# design.net
KiCad netlist of a schematic drawn in EasyEDA Pro
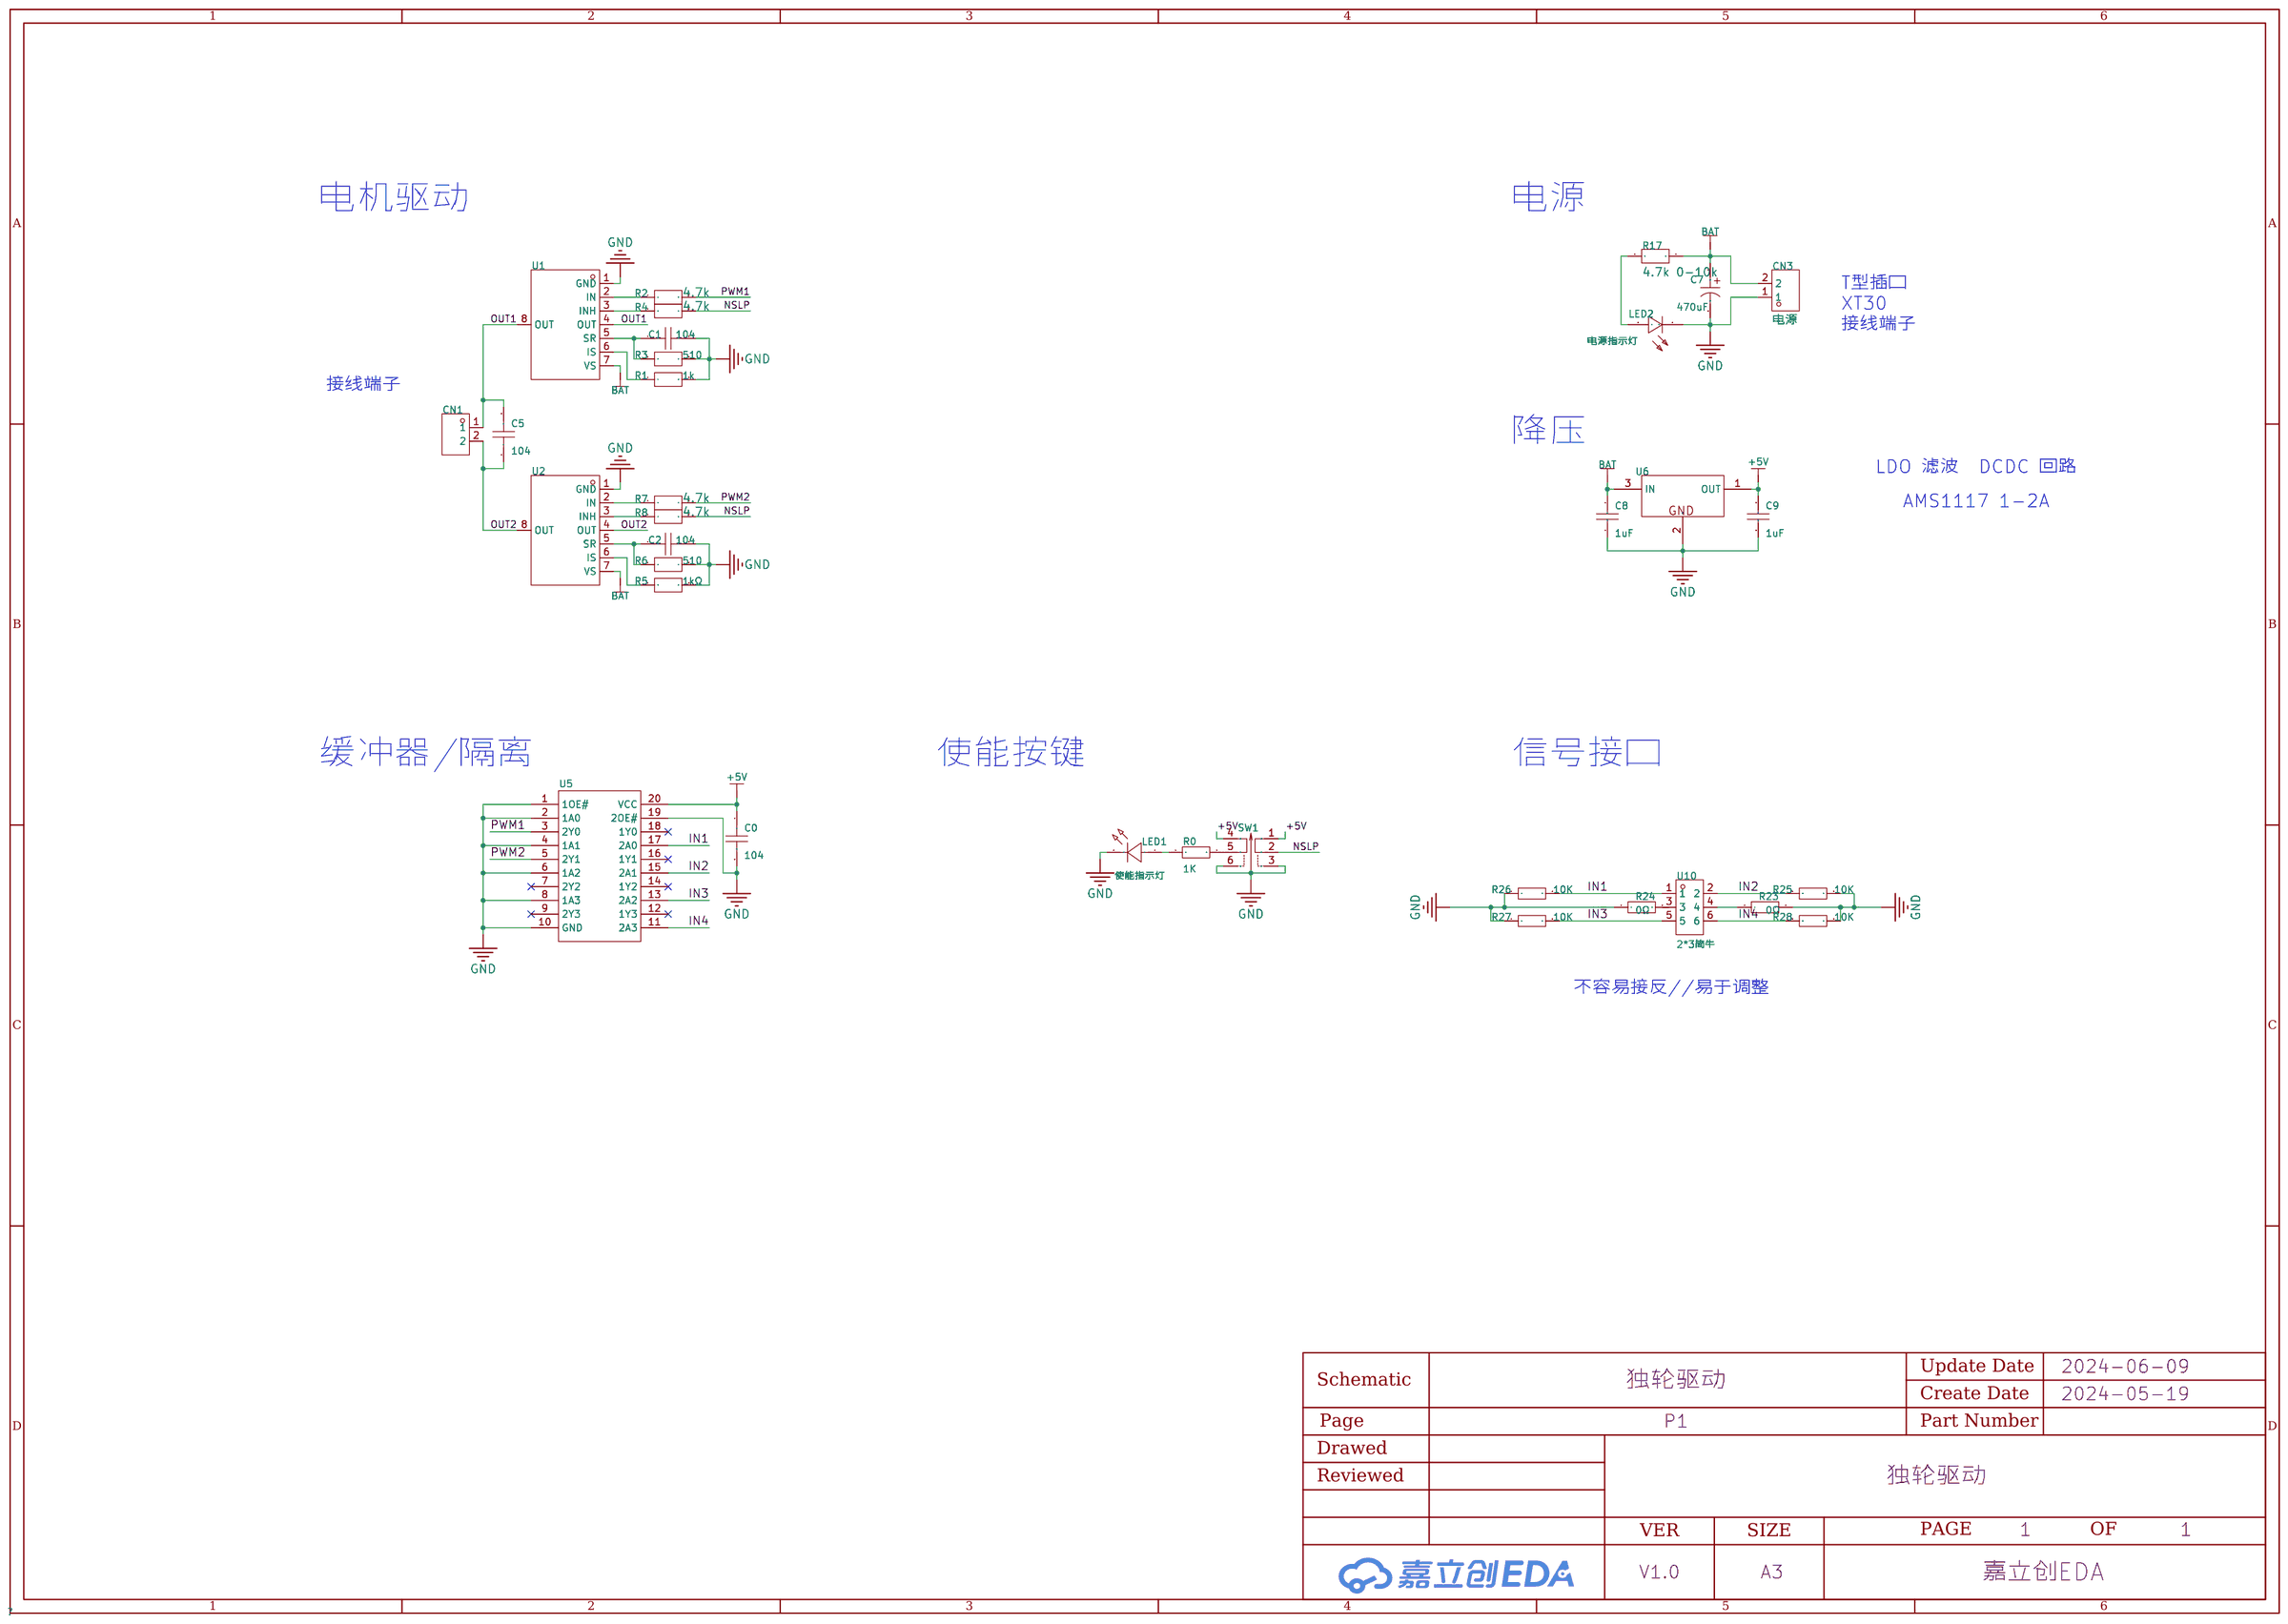
[diagram p0: schematic sheet]

(export (version "E")
  (design (tool "Eeschema 10.0.6"))
  (components
    (comp (ref "C0")
      (value "104")
      (footprint "easyedapro:C0603_1")
      (description "容值:100nF;精度:±10%;额定电压:50V;温度系数:X7R;")
      (libsource (lib "easyedapro") (part "C1210X7R475K630NT"))
    )
    (comp (ref "C1")
      (value "104")
      (footprint "easyedapro:C0603_1")
      (description "容值:100nF;精度:±10%;额定电压:50V;温度系数:X7R;")
      (libsource (lib "easyedapro") (part "C1210X7R475K630NT"))
    )
    (comp (ref "C2")
      (value "104")
      (footprint "easyedapro:C0603_1")
      (description "容值:100nF;精度:±10%;额定电压:50V;温度系数:X7R;")
      (libsource (lib "easyedapro") (part "C1210X7R475K630NT"))
    )
    (comp (ref "C5")
      (value "104")
      (footprint "easyedapro:C0603_1")
      (description "容值:100nF;精度:±10%;额定电压:50V;温度系数:X7R;")
      (libsource (lib "easyedapro") (part "C1210X7R475K630NT"))
    )
    (comp (ref "C7")
      (value "470uF")
      (footprint "easyedapro:CAP-SMD_BD8.0-L8.3-W8.3-LS9.1-FD")
      (description "容值:470uF;精度:±20%;额定电压:25V;电容体直径:-;电容体长度:-;纹波电流:-;等效串联电阻:-;工作寿命:-;")
      (fields (field (name "Manufacturer Part") "RVT1E471M0810") (field (name "Manufacturer") "HONOR(荣誉)"))
      (libsource (lib "easyedapro") (part "RVT1E471M0810"))
    )
    (comp (ref "C8")
      (value "1uF")
      (footprint "easyedapro:C0603_1")
      (description "温度系数:X5R;精度:±10%;额定电压:50V;容值:1uF;")
      (fields
        (field (name "Manufacturer Part") "CL10A105KB8NNNC")
        (field (name "Manufacturer") "SAMSUNG(三星)")
      )
      (libsource (lib "easyedapro") (part "CL10A105KB8NNNC"))
    )
    (comp (ref "C9")
      (value "1uF")
      (footprint "easyedapro:C0603_1")
      (description "温度系数:X5R;精度:±10%;额定电压:50V;容值:1uF;")
      (fields
        (field (name "Manufacturer Part") "CL10A105KB8NNNC")
        (field (name "Manufacturer") "SAMSUNG(三星)")
      )
      (libsource (lib "easyedapro") (part "CL10A105KB8NNNC"))
    )
    (comp (ref "CN1")
      (value "电机1")
      (footprint "easyedapro:CONN-TH_P5.00_KF301-5.0-2P")
      (description "间距:5mm;排数:1;每排PIN数:2;安装方式:直针;额定电流:17A;额定电压:250V;线规 - AWG:14~22;线规 - mm?:1.5;工作温度范围:-30~+120;颜色:蓝色;")
      (fields (field (name "Manufacturer Part") "KF301-5.0-2P") (field (name "Manufacturer") "KEFA(科发)"))
      (libsource (lib "easyedapro") (part "KF301-5.0-2P"))
    )
    (comp (ref "CN3")
      (value "电源")
      (footprint "easyedapro:CONN-TH_P5.00_KF301-5.0-2P")
      (description "间距:5mm;排数:1;每排PIN数:2;安装方式:直针;额定电流:17A;额定电压:250V;线规 - AWG:14~22;线规 - mm?:1.5;工作温度范围:-30~+120;颜色:蓝色;")
      (fields (field (name "Manufacturer Part") "KF301-5.0-2P") (field (name "Manufacturer") "KEFA(科发)"))
      (libsource (lib "easyedapro") (part "KF301-5.0-2P"))
    )
    (comp (ref "LED1")
      (value "使能指示灯")
      (footprint "easyedapro:LED-SMD_L1.6-W0.8-FD_GREEN")
      (fields
        (field (name "Manufacturer Part") "19-213/GVC-AMNB/3T")
        (field (name "Manufacturer") "EVERLIGHT(台湾亿光)")
      )
      (libsource (lib "easyedapro") (part "19-213/GVC-AMNB/3T_C883167"))
    )
    (comp (ref "LED2")
      (value "电源指示灯")
      (footprint "easyedapro:LED0603-RD_RED")
      (description "发光颜色:红灯;")
      (fields (field (name "Manufacturer Part") "NCD0603R1") (field (name "Manufacturer") "国星光电"))
      (libsource (lib "easyedapro") (part "FC-DA1608HRK-620D"))
    )
    (comp (ref "R0") (value "1K") (footprint "easyedapro:R0603") (libsource (lib "easyedapro") (part "电阻")))
    (comp (ref "R1")
      (value "1k")
      (footprint "easyedapro:R0603")
      (description "电阻类型:厚膜电阻;阻值:510Ω;精度:±5%;功率:100mW;温度系数:±100ppm/;最大工作电压:50V;工作温度范围:-55~+155;")
      (fields (field (name "Manufacturer Part") "FRC0603J511 TS") (field (name "Manufacturer") "FOJAN(富捷)"))
      (libsource (lib "easyedapro") (part "FRC0603J511 TS"))
    )
    (comp (ref "R2")
      (value "4.7k")
      (footprint "easyedapro:R0603")
      (fields (field (name "Manufacturer Part") "FRC0603J472 TS") (field (name "Manufacturer") "FOJAN(富捷)"))
      (libsource (lib "easyedapro") (part "FRC0603J472 TS"))
    )
    (comp (ref "R3")
      (value "510")
      (footprint "easyedapro:R0603")
      (description "电阻类型:厚膜电阻;阻值:510Ω;精度:±5%;功率:100mW;温度系数:±100ppm/;最大工作电压:50V;工作温度范围:-55~+155;")
      (fields (field (name "Manufacturer Part") "FRC0603J511 TS") (field (name "Manufacturer") "FOJAN(富捷)"))
      (libsource (lib "easyedapro") (part "FRC0603J511 TS"))
    )
    (comp (ref "R4")
      (value "4.7k")
      (footprint "easyedapro:R0603")
      (fields (field (name "Manufacturer Part") "FRC0603J472 TS") (field (name "Manufacturer") "FOJAN(富捷)"))
      (libsource (lib "easyedapro") (part "FRC0603J472 TS"))
    )
    (comp (ref "R5")
      (value "1kΩ")
      (footprint "easyedapro:R0603")
      (description "电阻类型:厚膜电阻;阻值:1kΩ;精度:±5%;功率:100mW;温度系数:±100ppm/;最大工作电压:50V;工作温度范围:-55~+155;")
      (fields (field (name "Manufacturer Part") "FRC0603J102 TS") (field (name "Manufacturer") "FOJAN(富捷)"))
      (libsource (lib "easyedapro") (part "FRC0603J102 TS"))
    )
    (comp (ref "R6")
      (value "510")
      (footprint "easyedapro:R0603")
      (description "电阻类型:厚膜电阻;阻值:510Ω;精度:±5%;功率:100mW;温度系数:±100ppm/;最大工作电压:50V;工作温度范围:-55~+155;")
      (fields (field (name "Manufacturer Part") "FRC0603J511 TS") (field (name "Manufacturer") "FOJAN(富捷)"))
      (libsource (lib "easyedapro") (part "FRC0603J511 TS"))
    )
    (comp (ref "R7")
      (value "4.7k")
      (footprint "easyedapro:R0603")
      (fields (field (name "Manufacturer Part") "FRC0603J472 TS") (field (name "Manufacturer") "FOJAN(富捷)"))
      (libsource (lib "easyedapro") (part "FRC0603J472 TS"))
    )
    (comp (ref "R8")
      (value "4.7k")
      (footprint "easyedapro:R0603")
      (fields (field (name "Manufacturer Part") "FRC0603J472 TS") (field (name "Manufacturer") "FOJAN(富捷)"))
      (libsource (lib "easyedapro") (part "FRC0603J472 TS"))
    )
    (comp (ref "R17")
      (value "4.7k 0-10k")
      (footprint "easyedapro:R0603")
      (fields (field (name "Manufacturer Part") "FRC0603J472 TS") (field (name "Manufacturer") "FOJAN(富捷)"))
      (libsource (lib "easyedapro") (part "FRC0603J472 TS"))
    )
    (comp (ref "R23")
      (value "0Ω")
      (footprint "easyedapro:R0603")
      (description "电阻类型:厚膜电阻;阻值:0Ω;精度:-;功率:100mW;温度系数:-;最大工作电压:150V;工作温度范围:-55~+155;")
      (fields (field (name "Manufacturer Part") "ERJ3GEY0R00V") (field (name "Manufacturer") "PANASONIC(松下)"))
      (libsource (lib "easyedapro") (part "ERJ-3GEY0R00V"))
    )
    (comp (ref "R24")
      (value "0Ω")
      (footprint "easyedapro:R0603")
      (description "电阻类型:厚膜电阻;阻值:0Ω;精度:-;功率:100mW;温度系数:-;最大工作电压:150V;工作温度范围:-55~+155;")
      (fields (field (name "Manufacturer Part") "ERJ3GEY0R00V") (field (name "Manufacturer") "PANASONIC(松下)"))
      (libsource (lib "easyedapro") (part "ERJ-3GEY0R00V"))
    )
    (comp (ref "R25")
      (value "10K")
      (footprint "easyedapro:R0603")
      (description "电阻类型:厚膜电阻;阻值:0Ω;精度:-;功率:100mW;温度系数:-;最大工作电压:150V;工作温度范围:-55~+155;")
      (fields (field (name "Manufacturer Part") "ERJ3GEY0R00V") (field (name "Manufacturer") "PANASONIC(松下)"))
      (libsource (lib "easyedapro") (part "ERJ-3GEY0R00V"))
    )
    (comp (ref "R26")
      (value "10K")
      (footprint "easyedapro:R0603")
      (description "电阻类型:厚膜电阻;阻值:0Ω;精度:-;功率:100mW;温度系数:-;最大工作电压:150V;工作温度范围:-55~+155;")
      (fields (field (name "Manufacturer Part") "ERJ3GEY0R00V") (field (name "Manufacturer") "PANASONIC(松下)"))
      (libsource (lib "easyedapro") (part "ERJ-3GEY0R00V"))
    )
    (comp (ref "R27")
      (value "10K")
      (footprint "easyedapro:R0603")
      (description "电阻类型:厚膜电阻;阻值:0Ω;精度:-;功率:100mW;温度系数:-;最大工作电压:150V;工作温度范围:-55~+155;")
      (fields (field (name "Manufacturer Part") "ERJ3GEY0R00V") (field (name "Manufacturer") "PANASONIC(松下)"))
      (libsource (lib "easyedapro") (part "ERJ-3GEY0R00V"))
    )
    (comp (ref "R28")
      (value "10K")
      (footprint "easyedapro:R0603")
      (description "电阻类型:厚膜电阻;阻值:0Ω;精度:-;功率:100mW;温度系数:-;最大工作电压:150V;工作温度范围:-55~+155;")
      (fields (field (name "Manufacturer Part") "ERJ3GEY0R00V") (field (name "Manufacturer") "PANASONIC(松下)"))
      (libsource (lib "easyedapro") (part "ERJ-3GEY0R00V"))
    )
    (comp (ref "SW1")
      (value "使能开关")
      (footprint "easyedapro:SW-TH_6P-L5.8-W5.8-P2.00-LS4.5-BL")
      (fields (field (name "Manufacturer Part") "PB22E60L") (field (name "Manufacturer") "CIKI(皓富)"))
      (libsource (lib "easyedapro") (part "PB22E60L"))
    )
    (comp (ref "U1")
      (value "BTN7971BAUMA1")
      (footprint "easyedapro:TO-263-7_L10.2-W10.4-P1.27-LS14.4-BR")
      (fields (field (name "Manufacturer") "Infineon(英飞凌)"))
      (libsource (lib "easyedapro") (part "BTN7971BAUMA1"))
    )
    (comp (ref "U2")
      (value "BTN7971BAUMA1")
      (footprint "easyedapro:TO-263-7_L10.2-W10.4-P1.27-LS14.4-BR")
      (fields (field (name "Manufacturer") "Infineon(英飞凌)"))
      (libsource (lib "easyedapro") (part "BTN7971BAUMA1"))
    )
    (comp (ref "U5")
      (value "74HC244PW,118")
      (footprint "easyedapro:TSSOP-20_L6.5-W4.4-P0.65-LS6.4-BL")
      (fields (field (name "Manufacturer") "Nexperia(安世)"))
      (libsource (lib "easyedapro") (part "74HC244PW,118"))
    )
    (comp (ref "U6")
      (value "~")
      (footprint "easyedapro:SOT-89-3_L4.5-W2.5-P1.50-LS4.2-BR")
      (fields (field (name "Manufacturer Part") "UMW78L05") (field (name "Manufacturer") "UMW(友台半导体)"))
      (libsource (lib "easyedapro") (part "UMW78L05"))
    )
    (comp (ref "U10")
      (value "2*3简牛")
      (footprint "easyedapro:CONN-TH_6P-P2.54_KINGHELM_KH-2.54PH180-2X3P-L8.9")
      (description "连接器类型:简牛座;间距:2.54mm;每排PIN数:3;排数:2;封装形式:直插;")
      (fields (field (name "Manufacturer") "kinghelm(金航标)"))
      (libsource (lib "easyedapro") (part "KH-2.54PH180-2X3P-L8.9"))
    )
  )
  (nets
    (net (code "1") (name "+5V") (class "Default")
      (node (ref "C0") (pin "1") (pinfunction "1_1") (pintype "input"))
      (node (ref "C9") (pin "2") (pinfunction "2_2") (pintype "input"))
      (node (ref "SW1") (pin "1") (pinfunction "1_1") (pintype "input"))
      (node (ref "SW1") (pin "4") (pinfunction "4_4") (pintype "input"))
      (node (ref "U5") (pin "20") (pinfunction "VCC_20") (pintype "input"))
      (node (ref "U6") (pin "1") (pinfunction "OUT_1") (pintype "input"))
    )
    (net (code "2") (name "/IN1") (class "Default")
      (node (ref "R26") (pin "2") (pinfunction "2_2") (pintype "input"))
      (node (ref "U10") (pin "1") (pinfunction "1_1") (pintype "input"))
      (node (ref "U5") (pin "17") (pinfunction "2A0_17") (pintype "input"))
    )
    (net (code "3") (name "/IN2") (class "Default")
      (node (ref "R25") (pin "1") (pinfunction "1_1") (pintype "input"))
      (node (ref "U10") (pin "2") (pinfunction "2_2") (pintype "input"))
      (node (ref "U5") (pin "15") (pinfunction "2A1_15") (pintype "input"))
    )
    (net (code "4") (name "/IN3") (class "Default")
      (node (ref "R27") (pin "2") (pinfunction "2_2") (pintype "input"))
      (node (ref "U10") (pin "5") (pinfunction "5_5") (pintype "input"))
      (node (ref "U5") (pin "13") (pinfunction "2A2_13") (pintype "input"))
    )
    (net (code "5") (name "/IN4") (class "Default")
      (node (ref "R28") (pin "1") (pinfunction "1_1") (pintype "input"))
      (node (ref "U10") (pin "6") (pinfunction "6_6") (pintype "input"))
      (node (ref "U5") (pin "11") (pinfunction "2A3_11") (pintype "input"))
    )
    (net (code "6") (name "/NSLP") (class "Default")
      (node (ref "R4") (pin "2") (pinfunction "2_2") (pintype "input"))
      (node (ref "R8") (pin "2") (pinfunction "2_2") (pintype "input"))
      (node (ref "SW1") (pin "2") (pinfunction "2_2") (pintype "input"))
    )
    (net (code "7") (name "/OUT1") (class "Default")
      (node (ref "C5") (pin "2") (pinfunction "2_2") (pintype "input"))
      (node (ref "CN1") (pin "1") (pinfunction "1_1") (pintype "input"))
      (node (ref "U1") (pin "4") (pinfunction "OUT_4") (pintype "input"))
      (node (ref "U1") (pin "8") (pinfunction "OUT_8") (pintype "input"))
    )
    (net (code "8") (name "/OUT2") (class "Default")
      (node (ref "C5") (pin "1") (pinfunction "1_1") (pintype "input"))
      (node (ref "CN1") (pin "2") (pinfunction "2_2") (pintype "input"))
      (node (ref "U2") (pin "4") (pinfunction "OUT_4") (pintype "input"))
      (node (ref "U2") (pin "8") (pinfunction "OUT_8") (pintype "input"))
    )
    (net (code "9") (name "/PWM1") (class "Default")
      (node (ref "R2") (pin "2") (pinfunction "2_2") (pintype "input"))
      (node (ref "U5") (pin "3") (pinfunction "2Y0_3") (pintype "input"))
    )
    (net (code "10") (name "/PWM2") (class "Default")
      (node (ref "R7") (pin "2") (pinfunction "2_2") (pintype "input"))
      (node (ref "U5") (pin "5") (pinfunction "2Y1_5") (pintype "input"))
    )
    (net (code "11") (name "BAT") (class "Default")
      (node (ref "C7") (pin "1") (pinfunction "1_1") (pintype "input"))
      (node (ref "C8") (pin "2") (pinfunction "2_2") (pintype "input"))
      (node (ref "CN3") (pin "2") (pinfunction "2_2") (pintype "input"))
      (node (ref "R17") (pin "1") (pinfunction "1_1") (pintype "input"))
      (node (ref "U1") (pin "7") (pinfunction "VS_7") (pintype "input"))
      (node (ref "U2") (pin "7") (pinfunction "VS_7") (pintype "input"))
      (node (ref "U6") (pin "3") (pinfunction "IN_3") (pintype "input"))
    )
    (net (code "12") (name "GND") (class "Default")
      (node (ref "C0") (pin "2") (pinfunction "2_2") (pintype "input"))
      (node (ref "C1") (pin "2") (pinfunction "2_2") (pintype "input"))
      (node (ref "C2") (pin "2") (pinfunction "2_2") (pintype "input"))
      (node (ref "C7") (pin "2") (pinfunction "2_2") (pintype "input"))
      (node (ref "C8") (pin "1") (pinfunction "1_1") (pintype "input"))
      (node (ref "C9") (pin "1") (pinfunction "1_1") (pintype "input"))
      (node (ref "CN3") (pin "1") (pinfunction "1_1") (pintype "input"))
      (node (ref "LED1") (pin "2") (pinfunction "A_2") (pintype "input"))
      (node (ref "LED2") (pin "1") (pinfunction "K_1") (pintype "input"))
      (node (ref "R1") (pin "2") (pinfunction "2_2") (pintype "input"))
      (node (ref "R23") (pin "2") (pinfunction "2_2") (pintype "input"))
      (node (ref "R24") (pin "1") (pinfunction "1_1") (pintype "input"))
      (node (ref "R25") (pin "2") (pinfunction "2_2") (pintype "input"))
      (node (ref "R26") (pin "1") (pinfunction "1_1") (pintype "input"))
      (node (ref "R27") (pin "1") (pinfunction "1_1") (pintype "input"))
      (node (ref "R28") (pin "2") (pinfunction "2_2") (pintype "input"))
      (node (ref "R3") (pin "2") (pinfunction "2_2") (pintype "input"))
      (node (ref "R5") (pin "2") (pinfunction "2_2") (pintype "input"))
      (node (ref "R6") (pin "2") (pinfunction "2_2") (pintype "input"))
      (node (ref "SW1") (pin "3") (pinfunction "3_3") (pintype "input"))
      (node (ref "SW1") (pin "6") (pinfunction "6_6") (pintype "input"))
      (node (ref "U1") (pin "1") (pinfunction "GND_1") (pintype "input"))
      (node (ref "U2") (pin "1") (pinfunction "GND_1") (pintype "input"))
      (node (ref "U5") (pin "1") (pinfunction "1OE#_1") (pintype "input"))
      (node (ref "U5") (pin "10") (pinfunction "GND_10") (pintype "input"))
      (node (ref "U5") (pin "19") (pinfunction "2OE#_19") (pintype "input"))
      (node (ref "U5") (pin "2") (pinfunction "1A0_2") (pintype "input"))
      (node (ref "U5") (pin "4") (pinfunction "1A1_4") (pintype "input"))
      (node (ref "U5") (pin "6") (pinfunction "1A2_6") (pintype "input"))
      (node (ref "U5") (pin "8") (pinfunction "1A3_8") (pintype "input"))
      (node (ref "U6") (pin "2") (pinfunction "GND_2") (pintype "input"))
    )
    (net (code "13") (name "Net-(LED1-K)") (class "Default")
      (node (ref "LED1") (pin "1") (pinfunction "K_1") (pintype "input"))
      (node (ref "R0") (pin "1") (pinfunction "1_1") (pintype "input"))
    )
    (net (code "14") (name "Net-(LED2-A)") (class "Default")
      (node (ref "LED2") (pin "2") (pinfunction "A_2") (pintype "input"))
      (node (ref "R17") (pin "2") (pinfunction "2_2") (pintype "input"))
    )
    (net (code "15") (name "Net-(R0-Pad2)") (class "Default")
      (node (ref "R0") (pin "2") (pinfunction "2_2") (pintype "input"))
      (node (ref "SW1") (pin "5") (pinfunction "5_5") (pintype "input"))
    )
    (net (code "16") (name "Net-(R23-Pad1)") (class "Default")
      (node (ref "R23") (pin "1") (pinfunction "1_1") (pintype "input"))
      (node (ref "U10") (pin "4") (pinfunction "4_4") (pintype "input"))
    )
    (net (code "17") (name "Net-(R24-Pad2)") (class "Default")
      (node (ref "R24") (pin "2") (pinfunction "2_2") (pintype "input"))
      (node (ref "U10") (pin "3") (pinfunction "3_3") (pintype "input"))
    )
    (net (code "18") (name "Net-(U1-IN)") (class "Default")
      (node (ref "R2") (pin "1") (pinfunction "1_1") (pintype "input"))
      (node (ref "U1") (pin "2") (pinfunction "IN_2") (pintype "input"))
    )
    (net (code "19") (name "Net-(U1-INH)") (class "Default")
      (node (ref "R4") (pin "1") (pinfunction "1_1") (pintype "input"))
      (node (ref "U1") (pin "3") (pinfunction "INH_3") (pintype "input"))
    )
    (net (code "20") (name "Net-(U1-IS)") (class "Default")
      (node (ref "R1") (pin "1") (pinfunction "1_1") (pintype "input"))
      (node (ref "U1") (pin "6") (pinfunction "IS_6") (pintype "input"))
    )
    (net (code "21") (name "Net-(U1-SR)") (class "Default")
      (node (ref "C1") (pin "1") (pinfunction "1_1") (pintype "input"))
      (node (ref "R3") (pin "1") (pinfunction "1_1") (pintype "input"))
      (node (ref "U1") (pin "5") (pinfunction "SR_5") (pintype "input"))
    )
    (net (code "22") (name "Net-(U2-IN)") (class "Default")
      (node (ref "R7") (pin "1") (pinfunction "1_1") (pintype "input"))
      (node (ref "U2") (pin "2") (pinfunction "IN_2") (pintype "input"))
    )
    (net (code "23") (name "Net-(U2-INH)") (class "Default")
      (node (ref "R8") (pin "1") (pinfunction "1_1") (pintype "input"))
      (node (ref "U2") (pin "3") (pinfunction "INH_3") (pintype "input"))
    )
    (net (code "24") (name "Net-(U2-IS)") (class "Default")
      (node (ref "R5") (pin "1") (pinfunction "1_1") (pintype "input"))
      (node (ref "U2") (pin "6") (pinfunction "IS_6") (pintype "input"))
    )
    (net (code "25") (name "Net-(U2-SR)") (class "Default")
      (node (ref "C2") (pin "1") (pinfunction "1_1") (pintype "input"))
      (node (ref "R6") (pin "1") (pinfunction "1_1") (pintype "input"))
      (node (ref "U2") (pin "5") (pinfunction "SR_5") (pintype "input"))
    )
    (net (code "26") (name "unconnected-(U5-1Y0-Pad18)") (class "Default")
      (node (ref "U5") (pin "18") (pinfunction "1Y0_18") (pintype "input+no_connect"))
    )
    (net (code "27") (name "unconnected-(U5-1Y1-Pad16)") (class "Default")
      (node (ref "U5") (pin "16") (pinfunction "1Y1_16") (pintype "input+no_connect"))
    )
    (net (code "28") (name "unconnected-(U5-1Y2-Pad14)") (class "Default")
      (node (ref "U5") (pin "14") (pinfunction "1Y2_14") (pintype "input+no_connect"))
    )
    (net (code "29") (name "unconnected-(U5-1Y3-Pad12)") (class "Default")
      (node (ref "U5") (pin "12") (pinfunction "1Y3_12") (pintype "input+no_connect"))
    )
    (net (code "30") (name "unconnected-(U5-2Y2-Pad7)") (class "Default")
      (node (ref "U5") (pin "7") (pinfunction "2Y2_7") (pintype "input+no_connect"))
    )
    (net (code "31") (name "unconnected-(U5-2Y3-Pad9)") (class "Default")
      (node (ref "U5") (pin "9") (pinfunction "2Y3_9") (pintype "input+no_connect"))
    )
  )
)
